# LPC1768_1.net
KiCad netlist of a schematic drawn in Altium Designer
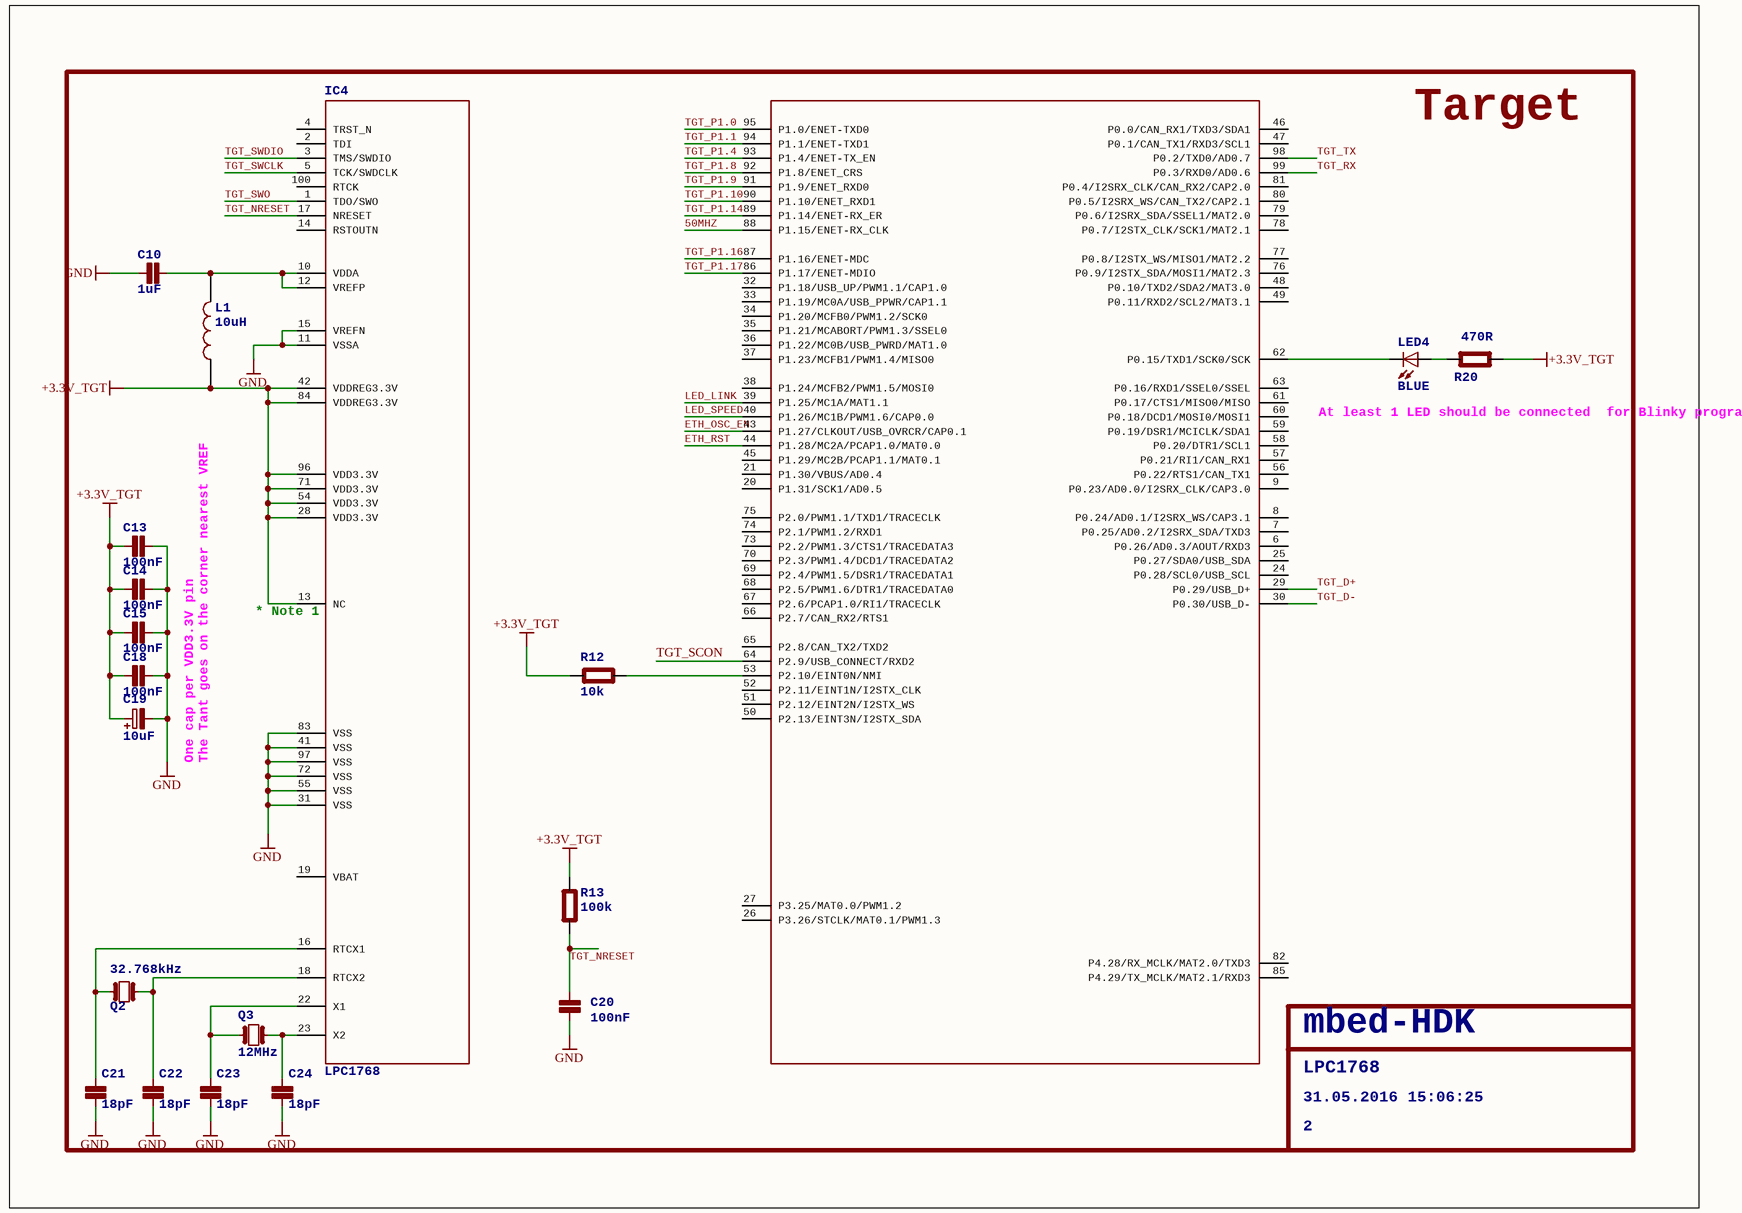
[diagram p0: LPC1768_1.SchDoc]

(export (version "E")
  (design (tool "Eeschema 10.0.6"))
  (components
    (comp (ref "C10") (value "1uF") (footprint "0603") (libsource (lib "") (part "C0603_2")))
    (comp (ref "C13") (value "100nF") (footprint "0603") (libsource (lib "mbed-HDK") (part "C0603")))
    (comp (ref "C14") (value "100nF") (footprint "0603") (libsource (lib "mbed-HDK") (part "C0603")))
    (comp (ref "C15") (value "100nF") (footprint "0603") (libsource (lib "mbed-HDK") (part "C0603")))
    (comp (ref "C18") (value "100nF") (footprint "0603") (libsource (lib "mbed-HDK") (part "C0603")))
    (comp (ref "C19") (value "10uF") (footprint "CASE-B") (libsource (lib "mbed-HDK") (part "C-POLB")))
    (comp (ref "C20") (value "100nF") (footprint "0603") (libsource (lib "") (part "C0603_1")))
    (comp (ref "C21") (value "18pF") (footprint "0603") (libsource (lib "") (part "C0603_1")))
    (comp (ref "C22") (value "18pF") (footprint "0603") (libsource (lib "") (part "C0603_1")))
    (comp (ref "C23") (value "18pF") (footprint "0603") (libsource (lib "") (part "C0603_1")))
    (comp (ref "C24") (value "18pF") (footprint "0603") (libsource (lib "") (part "C0603_1")))
    (comp (ref "IC4") (value "LPC1768") (footprint "LQFP100") (libsource (lib "mbed-HDK") (part "LPC1768")))
    (comp (ref "L1") (value "10uH") (footprint "0603") (libsource (lib "mbed-HDK") (part "L")))
    (comp (ref "LED4")
      (value "BLUE")
      (footprint "CHIPLED_0603")
      (libsource (lib "mbed-HDK") (part "LED0603"))
    )
    (comp (ref "Q2") (value "32.768kHz") (footprint "FC135") (libsource (lib "mbed-HDK") (part "Q_FC135")))
    (comp (ref "Q3") (value "12MHz") (footprint "HC49UP") (libsource (lib "mbed-HDK") (part "Q_HC49UP")))
    (comp (ref "R12") (value "10k") (footprint "0603") (libsource (lib "mbed-HDK") (part "R0603")))
    (comp (ref "R13") (value "100k") (footprint "0603") (libsource (lib "mbed-HDK") (part "R0603")))
    (comp (ref "R20") (value "470R") (footprint "0603") (libsource (lib "mbed-HDK") (part "R0603")))
  )
  (nets
    (net (code "1") (name "+3.3V_TGT") (class "Default")
      (node (ref "C13") (pin "1") (pinfunction "P$1_1") (pintype "passive"))
      (node (ref "C14") (pin "1") (pinfunction "P$1_1") (pintype "passive"))
      (node (ref "C15") (pin "1") (pinfunction "P$1_1") (pintype "passive"))
      (node (ref "C18") (pin "1") (pinfunction "P$1_1") (pintype "passive"))
      (node (ref "C19") (pin "1") (pinfunction "1_1") (pintype "passive"))
      (node (ref "IC4") (pin "13") (pinfunction "NC_13") (pintype "passive"))
      (node (ref "IC4") (pin "28") (pinfunction "VDD3.3V_28") (pintype "passive"))
      (node (ref "IC4") (pin "42") (pinfunction "VDDREG3.3V_42") (pintype "passive"))
      (node (ref "IC4") (pin "54") (pinfunction "VDD3.3V_54") (pintype "passive"))
      (node (ref "IC4") (pin "71") (pinfunction "VDD3.3V_71") (pintype "passive"))
      (node (ref "IC4") (pin "84") (pinfunction "VDDREG3.3V_84") (pintype "passive"))
      (node (ref "IC4") (pin "96") (pinfunction "VDD3.3V_96") (pintype "passive"))
      (node (ref "L1") (pin "1") (pinfunction "P$1_1") (pintype "passive"))
      (node (ref "R12") (pin "1") (pinfunction "P$1_1") (pintype "passive"))
      (node (ref "R13") (pin "2") (pinfunction "P$2_2") (pintype "passive"))
      (node (ref "R20") (pin "1") (pinfunction "P$1_1") (pintype "passive"))
    )
    (net (code "2") (name "/50MHZ") (class "Default")
      (node (ref "IC4") (pin "88") (pinfunction "P1.15/ENET-RX_CLK_88") (pintype "passive"))
    )
    (net (code "3") (name "/ETH_OSC_EN") (class "Default")
      (node (ref "IC4") (pin "43") (pinfunction "P1.27/CLKOUT/USB_OVRCR/CAP0.1_43") (pintype "passive"))
    )
    (net (code "4") (name "/ETH_RST") (class "Default")
      (node (ref "IC4") (pin "44") (pinfunction "P1.28/MC2A/PCAP1.0/MAT0.0_44") (pintype "passive"))
    )
    (net (code "5") (name "/LED_LINK") (class "Default")
      (node (ref "IC4") (pin "39") (pinfunction "P1.25/MC1A/MAT1.1_39") (pintype "passive"))
    )
    (net (code "6") (name "/LED_SPEED") (class "Default")
      (node (ref "IC4") (pin "40") (pinfunction "P1.26/MC1B/PWM1.6/CAP0.0_40") (pintype "passive"))
    )
    (net (code "7") (name "/TGT_D+") (class "Default")
      (node (ref "IC4") (pin "29") (pinfunction "P0.29/USB_D+_29") (pintype "passive"))
    )
    (net (code "8") (name "/TGT_D-") (class "Default")
      (node (ref "IC4") (pin "30") (pinfunction "P0.30/USB_D-_30") (pintype "passive"))
    )
    (net (code "9") (name "/TGT_NRESET") (class "Default")
      (node (ref "C20") (pin "2") (pinfunction "P$2_2") (pintype "passive"))
      (node (ref "IC4") (pin "17") (pinfunction "NRESET_17") (pintype "passive"))
      (node (ref "R13") (pin "1") (pinfunction "P$1_1") (pintype "passive"))
    )
    (net (code "10") (name "/TGT_P1.0") (class "Default")
      (node (ref "IC4") (pin "95") (pinfunction "P1.0/ENET-TXD0_95") (pintype "passive"))
    )
    (net (code "11") (name "/TGT_P1.1") (class "Default")
      (node (ref "IC4") (pin "94") (pinfunction "P1.1/ENET-TXD1_94") (pintype "passive"))
    )
    (net (code "12") (name "/TGT_P1.4") (class "Default")
      (node (ref "IC4") (pin "93") (pinfunction "P1.4/ENET-TX_EN_93") (pintype "passive"))
    )
    (net (code "13") (name "/TGT_P1.8") (class "Default")
      (node (ref "IC4") (pin "92") (pinfunction "P1.8/ENET_CRS_92") (pintype "passive"))
    )
    (net (code "14") (name "/TGT_P1.9") (class "Default")
      (node (ref "IC4") (pin "91") (pinfunction "P1.9/ENET_RXD0_91") (pintype "passive"))
    )
    (net (code "15") (name "/TGT_P1.10") (class "Default")
      (node (ref "IC4") (pin "90") (pinfunction "P1.10/ENET_RXD1_90") (pintype "passive"))
    )
    (net (code "16") (name "/TGT_P1.14") (class "Default")
      (node (ref "IC4") (pin "89") (pinfunction "P1.14/ENET-RX_ER_89") (pintype "passive"))
    )
    (net (code "17") (name "/TGT_P1.16") (class "Default")
      (node (ref "IC4") (pin "87") (pinfunction "P1.16/ENET-MDC_87") (pintype "passive"))
    )
    (net (code "18") (name "/TGT_P1.17") (class "Default")
      (node (ref "IC4") (pin "86") (pinfunction "P1.17/ENET-MDIO_86") (pintype "passive"))
    )
    (net (code "19") (name "/TGT_RX") (class "Default")
      (node (ref "IC4") (pin "99") (pinfunction "P0.3/RXD0/AD0.6_99") (pintype "passive"))
    )
    (net (code "20") (name "/TGT_SCON") (class "Default")
      (node (ref "IC4") (pin "64") (pinfunction "P2.9/USB_CONNECT/RXD2_64") (pintype "passive"))
    )
    (net (code "21") (name "/TGT_SWCLK") (class "Default")
      (node (ref "IC4") (pin "5") (pinfunction "TCK/SWDCLK_5") (pintype "passive"))
    )
    (net (code "22") (name "/TGT_SWDIO") (class "Default")
      (node (ref "IC4") (pin "3") (pinfunction "TMS/SWDIO_3") (pintype "passive"))
    )
    (net (code "23") (name "/TGT_SWO") (class "Default")
      (node (ref "IC4") (pin "1") (pinfunction "TDO/SWO_1") (pintype "passive"))
    )
    (net (code "24") (name "/TGT_TX") (class "Default")
      (node (ref "IC4") (pin "98") (pinfunction "P0.2/TXD0/AD0.7_98") (pintype "passive"))
    )
    (net (code "25") (name "GND") (class "Default")
      (node (ref "C10") (pin "2") (pinfunction "P$2_2") (pintype "passive"))
      (node (ref "C13") (pin "2") (pinfunction "P$2_2") (pintype "passive"))
      (node (ref "C14") (pin "2") (pinfunction "P$2_2") (pintype "passive"))
      (node (ref "C15") (pin "2") (pinfunction "P$2_2") (pintype "passive"))
      (node (ref "C18") (pin "2") (pinfunction "P$2_2") (pintype "passive"))
      (node (ref "C19") (pin "2") (pinfunction "2_2") (pintype "passive"))
      (node (ref "C20") (pin "1") (pinfunction "P$1_1") (pintype "passive"))
      (node (ref "C21") (pin "1") (pinfunction "P$1_1") (pintype "passive"))
      (node (ref "C22") (pin "1") (pinfunction "P$1_1") (pintype "passive"))
      (node (ref "C23") (pin "1") (pinfunction "P$1_1") (pintype "passive"))
      (node (ref "C24") (pin "1") (pinfunction "P$1_1") (pintype "passive"))
      (node (ref "IC4") (pin "11") (pinfunction "VSSA_11") (pintype "passive"))
      (node (ref "IC4") (pin "15") (pinfunction "VREFN_15") (pintype "passive"))
      (node (ref "IC4") (pin "31") (pinfunction "VSS_31") (pintype "passive"))
      (node (ref "IC4") (pin "41") (pinfunction "VSS_41") (pintype "passive"))
      (node (ref "IC4") (pin "55") (pinfunction "VSS_55") (pintype "passive"))
      (node (ref "IC4") (pin "72") (pinfunction "VSS_72") (pintype "passive"))
      (node (ref "IC4") (pin "83") (pinfunction "VSS_83") (pintype "passive"))
      (node (ref "IC4") (pin "97") (pinfunction "VSS_97") (pintype "passive"))
    )
    (net (code "26") (name "Net-(C10-P$1)") (class "Default")
      (node (ref "C10") (pin "1") (pinfunction "P$1_1") (pintype "passive"))
      (node (ref "IC4") (pin "10") (pinfunction "VDDA_10") (pintype "passive"))
      (node (ref "IC4") (pin "12") (pinfunction "VREFP_12") (pintype "passive"))
      (node (ref "L1") (pin "2") (pinfunction "P$2_2") (pintype "passive"))
    )
    (net (code "27") (name "Net-(C21-P$2)") (class "Default")
      (node (ref "C21") (pin "2") (pinfunction "P$2_2") (pintype "passive"))
      (node (ref "IC4") (pin "16") (pinfunction "RTCX1_16") (pintype "passive"))
      (node (ref "Q2") (pin "X2") (pinfunction "2_X2") (pintype "passive"))
    )
    (net (code "28") (name "Net-(C22-P$2)") (class "Default")
      (node (ref "C22") (pin "2") (pinfunction "P$2_2") (pintype "passive"))
      (node (ref "IC4") (pin "18") (pinfunction "RTCX2_18") (pintype "passive"))
      (node (ref "Q2") (pin "X1") (pinfunction "1_X1") (pintype "passive"))
    )
    (net (code "29") (name "Net-(C23-P$2)") (class "Default")
      (node (ref "C23") (pin "2") (pinfunction "P$2_2") (pintype "passive"))
      (node (ref "IC4") (pin "22") (pinfunction "X1_22") (pintype "passive"))
      (node (ref "Q3") (pin "1") (pinfunction "1_1") (pintype "passive"))
    )
    (net (code "30") (name "Net-(C24-P$2)") (class "Default")
      (node (ref "C24") (pin "2") (pinfunction "P$2_2") (pintype "passive"))
      (node (ref "IC4") (pin "23") (pinfunction "X2_23") (pintype "passive"))
      (node (ref "Q3") (pin "2") (pinfunction "2_2") (pintype "passive"))
    )
    (net (code "31") (name "Net-(IC4-P0.15{slash}TXD1{slash}SCK0{slash}SCK)") (class "Default")
      (node (ref "IC4") (pin "62") (pinfunction "P0.15/TXD1/SCK0/SCK_62") (pintype "passive"))
      (node (ref "LED4") (pin "C") (pinfunction "C_C") (pintype "passive"))
    )
    (net (code "32") (name "Net-(IC4-P2.10{slash}EINT0N{slash}NMI)") (class "Default")
      (node (ref "IC4") (pin "53") (pinfunction "P2.10/EINT0N/NMI_53") (pintype "passive"))
      (node (ref "R12") (pin "2") (pinfunction "P$2_2") (pintype "passive"))
    )
    (net (code "33") (name "Net-(R20-P$2)") (class "Default")
      (node (ref "LED4") (pin "A") (pinfunction "A_A") (pintype "passive"))
      (node (ref "R20") (pin "2") (pinfunction "P$2_2") (pintype "passive"))
    )
    (net (code "34") (name "unconnected-(IC4-P0.0{slash}CAN_RX1{slash}TXD3{slash}SDA1-Pad46)") (class "Default")
      (node (ref "IC4") (pin "46") (pinfunction "P0.0/CAN_RX1/TXD3/SDA1_46") (pintype "passive"))
    )
    (net (code "35") (name "unconnected-(IC4-P0.1{slash}CAN_TX1{slash}RXD3{slash}SCL1-Pad47)") (class "Default")
      (node (ref "IC4") (pin "47") (pinfunction "P0.1/CAN_TX1/RXD3/SCL1_47") (pintype "passive"))
    )
    (net (code "36") (name "unconnected-(IC4-P0.4{slash}I2SRX_CLK{slash}CAN_RX2{slash}CAP2.0-Pad81)") (class "Default")
      (node (ref "IC4") (pin "81") (pinfunction "P0.4/I2SRX_CLK/CAN_RX2/CAP2.0_81") (pintype "passive"))
    )
    (net (code "37") (name "unconnected-(IC4-P0.5{slash}I2SRX_WS{slash}CAN_TX2{slash}CAP2.1-Pad80)") (class "Default")
      (node (ref "IC4") (pin "80") (pinfunction "P0.5/I2SRX_WS/CAN_TX2/CAP2.1_80") (pintype "passive"))
    )
    (net (code "38") (name "unconnected-(IC4-P0.6{slash}I2SRX_SDA{slash}SSEL1{slash}MAT2.0-Pad79)") (class "Default")
      (node (ref "IC4") (pin "79") (pinfunction "P0.6/I2SRX_SDA/SSEL1/MAT2.0_79") (pintype "passive"))
    )
    (net (code "39") (name "unconnected-(IC4-P0.7{slash}I2STX_CLK{slash}SCK1{slash}MAT2.1-Pad78)") (class "Default")
      (node (ref "IC4") (pin "78") (pinfunction "P0.7/I2STX_CLK/SCK1/MAT2.1_78") (pintype "passive"))
    )
    (net (code "40") (name "unconnected-(IC4-P0.8{slash}I2STX_WS{slash}MISO1{slash}MAT2.2-Pad77)") (class "Default")
      (node (ref "IC4") (pin "77") (pinfunction "P0.8/I2STX_WS/MISO1/MAT2.2_77") (pintype "passive"))
    )
    (net (code "41") (name "unconnected-(IC4-P0.9{slash}I2STX_SDA{slash}MOSI1{slash}MAT2.3-Pad76)") (class "Default")
      (node (ref "IC4") (pin "76") (pinfunction "P0.9/I2STX_SDA/MOSI1/MAT2.3_76") (pintype "passive"))
    )
    (net (code "42") (name "unconnected-(IC4-P0.10{slash}TXD2{slash}SDA2{slash}MAT3.0-Pad48)") (class "Default")
      (node (ref "IC4") (pin "48") (pinfunction "P0.10/TXD2/SDA2/MAT3.0_48") (pintype "passive"))
    )
    (net (code "43") (name "unconnected-(IC4-P0.11{slash}RXD2{slash}SCL2{slash}MAT3.1-Pad49)") (class "Default")
      (node (ref "IC4") (pin "49") (pinfunction "P0.11/RXD2/SCL2/MAT3.1_49") (pintype "passive"))
    )
    (net (code "44") (name "unconnected-(IC4-P0.16{slash}RXD1{slash}SSEL0{slash}SSEL-Pad63)") (class "Default")
      (node (ref "IC4") (pin "63") (pinfunction "P0.16/RXD1/SSEL0/SSEL_63") (pintype "passive"))
    )
    (net (code "45") (name "unconnected-(IC4-P0.17{slash}CTS1{slash}MISO0{slash}MISO-Pad61)") (class "Default")
      (node (ref "IC4") (pin "61") (pinfunction "P0.17/CTS1/MISO0/MISO_61") (pintype "passive"))
    )
    (net (code "46") (name "unconnected-(IC4-P0.18{slash}DCD1{slash}MOSI0{slash}MOSI1-Pad60)") (class "Default")
      (node (ref "IC4") (pin "60") (pinfunction "P0.18/DCD1/MOSI0/MOSI1_60") (pintype "passive"))
    )
    (net (code "47") (name "unconnected-(IC4-P0.19{slash}DSR1{slash}MCICLK{slash}SDA1-Pad59)") (class "Default")
      (node (ref "IC4") (pin "59") (pinfunction "P0.19/DSR1/MCICLK/SDA1_59") (pintype "passive"))
    )
    (net (code "48") (name "unconnected-(IC4-P0.20{slash}DTR1{slash}SCL1-Pad58)") (class "Default")
      (node (ref "IC4") (pin "58") (pinfunction "P0.20/DTR1/SCL1_58") (pintype "passive"))
    )
    (net (code "49") (name "unconnected-(IC4-P0.21{slash}RI1{slash}CAN_RX1-Pad57)") (class "Default")
      (node (ref "IC4") (pin "57") (pinfunction "P0.21/RI1/CAN_RX1_57") (pintype "passive"))
    )
    (net (code "50") (name "unconnected-(IC4-P0.22{slash}RTS1{slash}CAN_TX1-Pad56)") (class "Default")
      (node (ref "IC4") (pin "56") (pinfunction "P0.22/RTS1/CAN_TX1_56") (pintype "passive"))
    )
    (net (code "51") (name "unconnected-(IC4-P0.23{slash}AD0.0{slash}I2SRX_CLK{slash}CAP3.0-Pad9)") (class "Default")
      (node (ref "IC4") (pin "9") (pinfunction "P0.23/AD0.0/I2SRX_CLK/CAP3.0_9") (pintype "passive"))
    )
    (net (code "52") (name "unconnected-(IC4-P0.24{slash}AD0.1{slash}I2SRX_WS{slash}CAP3.1-Pad8)") (class "Default")
      (node (ref "IC4") (pin "8") (pinfunction "P0.24/AD0.1/I2SRX_WS/CAP3.1_8") (pintype "passive"))
    )
    (net (code "53") (name "unconnected-(IC4-P0.25{slash}AD0.2{slash}I2SRX_SDA{slash}TXD3-Pad7)") (class "Default")
      (node (ref "IC4") (pin "7") (pinfunction "P0.25/AD0.2/I2SRX_SDA/TXD3_7") (pintype "passive"))
    )
    (net (code "54") (name "unconnected-(IC4-P0.26{slash}AD0.3{slash}AOUT{slash}RXD3-Pad6)") (class "Default")
      (node (ref "IC4") (pin "6") (pinfunction "P0.26/AD0.3/AOUT/RXD3_6") (pintype "passive"))
    )
    (net (code "55") (name "unconnected-(IC4-P0.27{slash}SDA0{slash}USB_SDA-Pad25)") (class "Default")
      (node (ref "IC4") (pin "25") (pinfunction "P0.27/SDA0/USB_SDA_25") (pintype "passive"))
    )
    (net (code "56") (name "unconnected-(IC4-P0.28{slash}SCL0{slash}USB_SCL-Pad24)") (class "Default")
      (node (ref "IC4") (pin "24") (pinfunction "P0.28/SCL0/USB_SCL_24") (pintype "passive"))
    )
    (net (code "57") (name "unconnected-(IC4-P1.18{slash}USB_UP{slash}PWM1.1{slash}CAP1.0-Pad32)") (class "Default")
      (node (ref "IC4") (pin "32") (pinfunction "P1.18/USB_UP/PWM1.1/CAP1.0_32") (pintype "passive"))
    )
    (net (code "58") (name "unconnected-(IC4-P1.19{slash}MC0A{slash}USB_PPWR{slash}CAP1.1-Pad33)") (class "Default")
      (node (ref "IC4") (pin "33") (pinfunction "P1.19/MC0A/USB_PPWR/CAP1.1_33") (pintype "passive"))
    )
    (net (code "59") (name "unconnected-(IC4-P1.20{slash}MCFB0{slash}PWM1.2{slash}SCK0-Pad34)") (class "Default")
      (node (ref "IC4") (pin "34") (pinfunction "P1.20/MCFB0/PWM1.2/SCK0_34") (pintype "passive"))
    )
    (net (code "60") (name "unconnected-(IC4-P1.21{slash}MCABORT{slash}PWM1.3{slash}SSEL0-Pad35)") (class "Default")
      (node (ref "IC4") (pin "35") (pinfunction "P1.21/MCABORT/PWM1.3/SSEL0_35") (pintype "passive"))
    )
    (net (code "61") (name "unconnected-(IC4-P1.22{slash}MC0B{slash}USB_PWRD{slash}MAT1.0-Pad36)") (class "Default")
      (node (ref "IC4") (pin "36") (pinfunction "P1.22/MC0B/USB_PWRD/MAT1.0_36") (pintype "passive"))
    )
    (net (code "62") (name "unconnected-(IC4-P1.23{slash}MCFB1{slash}PWM1.4{slash}MISO0-Pad37)") (class "Default")
      (node (ref "IC4") (pin "37") (pinfunction "P1.23/MCFB1/PWM1.4/MISO0_37") (pintype "passive"))
    )
    (net (code "63") (name "unconnected-(IC4-P1.24{slash}MCFB2{slash}PWM1.5{slash}MOSI0-Pad38)") (class "Default")
      (node (ref "IC4") (pin "38") (pinfunction "P1.24/MCFB2/PWM1.5/MOSI0_38") (pintype "passive"))
    )
    (net (code "64") (name "unconnected-(IC4-P1.29{slash}MC2B{slash}PCAP1.1{slash}MAT0.1-Pad45)") (class "Default")
      (node (ref "IC4") (pin "45") (pinfunction "P1.29/MC2B/PCAP1.1/MAT0.1_45") (pintype "passive"))
    )
    (net (code "65") (name "unconnected-(IC4-P1.30{slash}VBUS{slash}AD0.4-Pad21)") (class "Default")
      (node (ref "IC4") (pin "21") (pinfunction "P1.30/VBUS/AD0.4_21") (pintype "passive"))
    )
    (net (code "66") (name "unconnected-(IC4-P1.31{slash}SCK1{slash}AD0.5-Pad20)") (class "Default")
      (node (ref "IC4") (pin "20") (pinfunction "P1.31/SCK1/AD0.5_20") (pintype "passive"))
    )
    (net (code "67") (name "unconnected-(IC4-P2.0{slash}PWM1.1{slash}TXD1{slash}TRACECLK-Pad75)") (class "Default")
      (node (ref "IC4") (pin "75") (pinfunction "P2.0/PWM1.1/TXD1/TRACECLK_75") (pintype "passive"))
    )
    (net (code "68") (name "unconnected-(IC4-P2.1{slash}PWM1.2{slash}RXD1-Pad74)") (class "Default")
      (node (ref "IC4") (pin "74") (pinfunction "P2.1/PWM1.2/RXD1_74") (pintype "passive"))
    )
    (net (code "69") (name "unconnected-(IC4-P2.2{slash}PWM1.3{slash}CTS1{slash}TRACEDATA3-Pad73)") (class "Default")
      (node (ref "IC4") (pin "73") (pinfunction "P2.2/PWM1.3/CTS1/TRACEDATA3_73") (pintype "passive"))
    )
    (net (code "70") (name "unconnected-(IC4-P2.3{slash}PWM1.4{slash}DCD1{slash}TRACEDATA2-Pad70)") (class "Default")
      (node (ref "IC4") (pin "70") (pinfunction "P2.3/PWM1.4/DCD1/TRACEDATA2_70") (pintype "passive"))
    )
    (net (code "71") (name "unconnected-(IC4-P2.4{slash}PWM1.5{slash}DSR1{slash}TRACEDATA1-Pad69)") (class "Default")
      (node (ref "IC4") (pin "69") (pinfunction "P2.4/PWM1.5/DSR1/TRACEDATA1_69") (pintype "passive"))
    )
    (net (code "72") (name "unconnected-(IC4-P2.5{slash}PWM1.6{slash}DTR1{slash}TRACEDATA0-Pad68)") (class "Default")
      (node (ref "IC4") (pin "68") (pinfunction "P2.5/PWM1.6/DTR1/TRACEDATA0_68") (pintype "passive"))
    )
    (net (code "73") (name "unconnected-(IC4-P2.6{slash}PCAP1.0{slash}RI1{slash}TRACECLK-Pad67)") (class "Default")
      (node (ref "IC4") (pin "67") (pinfunction "P2.6/PCAP1.0/RI1/TRACECLK_67") (pintype "passive"))
    )
    (net (code "74") (name "unconnected-(IC4-P2.7{slash}CAN_RX2{slash}RTS1-Pad66)") (class "Default")
      (node (ref "IC4") (pin "66") (pinfunction "P2.7/CAN_RX2/RTS1_66") (pintype "passive"))
    )
    (net (code "75") (name "unconnected-(IC4-P2.8{slash}CAN_TX2{slash}TXD2-Pad65)") (class "Default")
      (node (ref "IC4") (pin "65") (pinfunction "P2.8/CAN_TX2/TXD2_65") (pintype "passive"))
    )
    (net (code "76") (name "unconnected-(IC4-P2.11{slash}EINT1N{slash}I2STX_CLK-Pad52)") (class "Default")
      (node (ref "IC4") (pin "52") (pinfunction "P2.11/EINT1N/I2STX_CLK_52") (pintype "passive"))
    )
    (net (code "77") (name "unconnected-(IC4-P2.12{slash}EINT2N{slash}I2STX_WS-Pad51)") (class "Default")
      (node (ref "IC4") (pin "51") (pinfunction "P2.12/EINT2N/I2STX_WS_51") (pintype "passive"))
    )
    (net (code "78") (name "unconnected-(IC4-P2.13{slash}EINT3N{slash}I2STX_SDA-Pad50)") (class "Default")
      (node (ref "IC4") (pin "50") (pinfunction "P2.13/EINT3N/I2STX_SDA_50") (pintype "passive"))
    )
    (net (code "79") (name "unconnected-(IC4-P3.25{slash}MAT0.0{slash}PWM1.2-Pad27)") (class "Default")
      (node (ref "IC4") (pin "27") (pinfunction "P3.25/MAT0.0/PWM1.2_27") (pintype "passive"))
    )
    (net (code "80") (name "unconnected-(IC4-P3.26{slash}STCLK{slash}MAT0.1{slash}PWM1.3-Pad26)") (class "Default")
      (node (ref "IC4") (pin "26") (pinfunction "P3.26/STCLK/MAT0.1/PWM1.3_26") (pintype "passive"))
    )
    (net (code "81") (name "unconnected-(IC4-P4.28{slash}RX_MCLK{slash}MAT2.0{slash}TXD3-Pad82)") (class "Default")
      (node (ref "IC4") (pin "82") (pinfunction "P4.28/RX_MCLK/MAT2.0/TXD3_82") (pintype "passive"))
    )
    (net (code "82") (name "unconnected-(IC4-P4.29{slash}TX_MCLK{slash}MAT2.1{slash}RXD3-Pad85)") (class "Default")
      (node (ref "IC4") (pin "85") (pinfunction "P4.29/TX_MCLK/MAT2.1/RXD3_85") (pintype "passive"))
    )
    (net (code "83") (name "unconnected-(IC4-RSTOUTN-Pad14)") (class "Default")
      (node (ref "IC4") (pin "14") (pinfunction "RSTOUTN_14") (pintype "passive"))
    )
    (net (code "84") (name "unconnected-(IC4-RTCK-Pad100)") (class "Default")
      (node (ref "IC4") (pin "100") (pinfunction "RTCK_100") (pintype "passive"))
    )
    (net (code "85") (name "unconnected-(IC4-TDI-Pad2)") (class "Default")
      (node (ref "IC4") (pin "2") (pinfunction "TDI_2") (pintype "passive"))
    )
    (net (code "86") (name "unconnected-(IC4-TRST_N-Pad4)") (class "Default")
      (node (ref "IC4") (pin "4") (pinfunction "TRST_N_4") (pintype "passive"))
    )
    (net (code "87") (name "unconnected-(IC4-VBAT-Pad19)") (class "Default")
      (node (ref "IC4") (pin "19") (pinfunction "VBAT_19") (pintype "passive"))
    )
  )
)
